# LED.net
KiCad netlist of a schematic drawn in Altium Designer
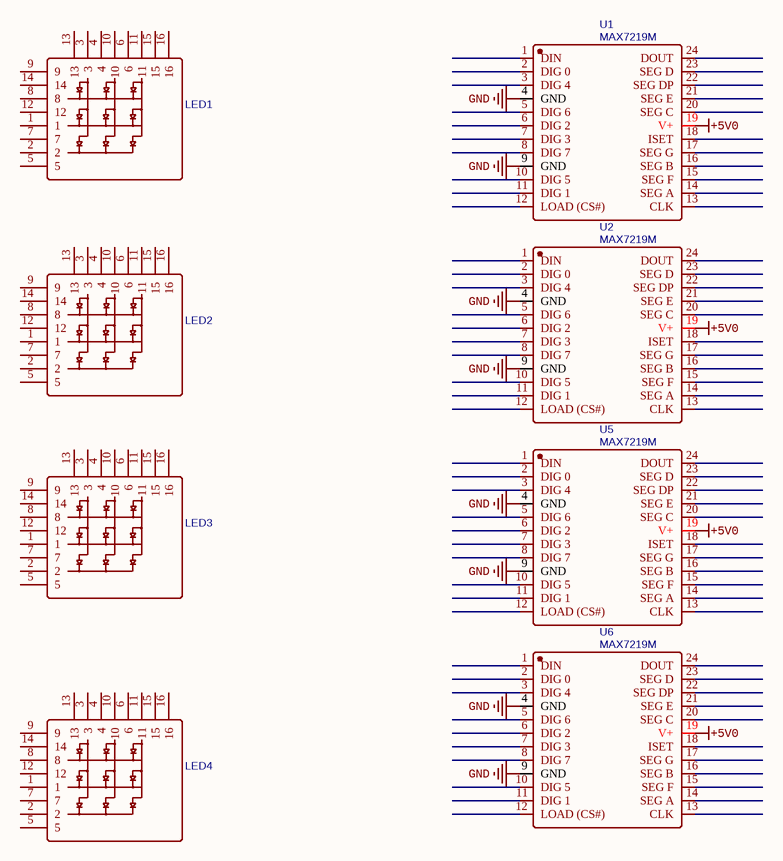
[diagram p0: LED.SchDoc]

(export (version "E")
  (design (tool "Eeschema 10.0.6"))
  (components
    (comp (ref "LED1")
      (value "~")
      (footprint "matrix_led")
      (fields
        (field (name "BOM_SUPPLIER PART") "C225986")
        (field (name "BOM_MANUFACTURER PART") "SLD0888DWC1BY")
        (field (name "CONTRIBUTOR") "LCSC")
      )
      (libsource (lib "altium-import") (part "root_0_SLD0888DWC1BY_"))
    )
    (comp (ref "LED2")
      (value "~")
      (footprint "matrix_led")
      (fields
        (field (name "BOM_SUPPLIER PART") "C225986")
        (field (name "BOM_MANUFACTURER PART") "SLD0888DWC1BY")
        (field (name "CONTRIBUTOR") "LCSC")
      )
      (libsource (lib "altium-import") (part "root_0_SLD0888DWC1BY_"))
    )
    (comp (ref "LED3")
      (value "~")
      (footprint "matrix_led")
      (fields
        (field (name "BOM_SUPPLIER PART") "C225986")
        (field (name "BOM_MANUFACTURER PART") "SLD0888DWC1BY")
        (field (name "CONTRIBUTOR") "LCSC")
      )
      (libsource (lib "altium-import") (part "root_0_SLD0888DWC1BY_"))
    )
    (comp (ref "LED4")
      (value "~")
      (footprint "matrix_led")
      (fields
        (field (name "BOM_SUPPLIER PART") "C225986")
        (field (name "BOM_MANUFACTURER PART") "SLD0888DWC1BY")
        (field (name "CONTRIBUTOR") "LCSC")
      )
      (libsource (lib "altium-import") (part "root_0_SLD0888DWC1BY_"))
    )
    (comp (ref "U1")
      (value "MAX7219M")
      (footprint "SOP-24_300mil")
      (fields (field (name "BOM_SUPPLIER PART") "C492110") (field (name "CONTRIBUTOR") "LCSC"))
      (libsource (lib "altium-import") (part "root_0_MAX7219M_"))
    )
    (comp (ref "U2")
      (value "MAX7219M")
      (footprint "SOP-24_300mil")
      (fields (field (name "BOM_SUPPLIER PART") "C492110") (field (name "CONTRIBUTOR") "LCSC"))
      (libsource (lib "altium-import") (part "root_0_MAX7219M_"))
    )
    (comp (ref "U5")
      (value "MAX7219M")
      (footprint "SOP-24_300mil")
      (fields (field (name "BOM_SUPPLIER PART") "C492110") (field (name "CONTRIBUTOR") "LCSC"))
      (libsource (lib "altium-import") (part "root_0_MAX7219M_"))
    )
    (comp (ref "U6")
      (value "MAX7219M")
      (footprint "SOP-24_300mil")
      (fields (field (name "BOM_SUPPLIER PART") "C492110") (field (name "CONTRIBUTOR") "LCSC"))
      (libsource (lib "altium-import") (part "root_0_MAX7219M_"))
    )
  )
  (nets
    (net (code "1") (name "+5V0") (class "Default")
      (node (ref "U1") (pin "19") (pinfunction "V+_19") (pintype "passive"))
      (node (ref "U2") (pin "19") (pinfunction "V+_19") (pintype "passive"))
      (node (ref "U5") (pin "19") (pinfunction "V+_19") (pintype "passive"))
      (node (ref "U6") (pin "19") (pinfunction "V+_19") (pintype "passive"))
    )
    (net (code "2") (name "GND") (class "Default")
      (node (ref "U1") (pin "4") (pinfunction "GND_4") (pintype "passive"))
      (node (ref "U1") (pin "9") (pinfunction "GND_9") (pintype "passive"))
      (node (ref "U2") (pin "4") (pinfunction "GND_4") (pintype "passive"))
      (node (ref "U2") (pin "9") (pinfunction "GND_9") (pintype "passive"))
      (node (ref "U5") (pin "4") (pinfunction "GND_4") (pintype "passive"))
      (node (ref "U5") (pin "9") (pinfunction "GND_9") (pintype "passive"))
      (node (ref "U6") (pin "4") (pinfunction "GND_4") (pintype "passive"))
      (node (ref "U6") (pin "9") (pinfunction "GND_9") (pintype "passive"))
    )
    (net (code "3") (name "unconnected-(LED1-Pad1)") (class "Default")
      (node (ref "LED1") (pin "1") (pinfunction "1_1") (pintype "passive"))
    )
    (net (code "4") (name "unconnected-(LED1-Pad2)") (class "Default")
      (node (ref "LED1") (pin "2") (pinfunction "2_2") (pintype "passive"))
    )
    (net (code "5") (name "unconnected-(LED1-Pad3)") (class "Default")
      (node (ref "LED1") (pin "3") (pinfunction "3_3") (pintype "passive"))
    )
    (net (code "6") (name "unconnected-(LED1-Pad4)") (class "Default")
      (node (ref "LED1") (pin "4") (pinfunction "4_4") (pintype "passive"))
    )
    (net (code "7") (name "unconnected-(LED1-Pad5)") (class "Default")
      (node (ref "LED1") (pin "5") (pinfunction "5_5") (pintype "passive"))
    )
    (net (code "8") (name "unconnected-(LED1-Pad6)") (class "Default")
      (node (ref "LED1") (pin "6") (pinfunction "6_6") (pintype "passive"))
    )
    (net (code "9") (name "unconnected-(LED1-Pad7)") (class "Default")
      (node (ref "LED1") (pin "7") (pinfunction "7_7") (pintype "passive"))
    )
    (net (code "10") (name "unconnected-(LED1-Pad8)") (class "Default")
      (node (ref "LED1") (pin "8") (pinfunction "8_8") (pintype "passive"))
    )
    (net (code "11") (name "unconnected-(LED1-Pad9)") (class "Default")
      (node (ref "LED1") (pin "9") (pinfunction "9_9") (pintype "passive"))
    )
    (net (code "12") (name "unconnected-(LED1-Pad10)") (class "Default")
      (node (ref "LED1") (pin "10") (pinfunction "10_10") (pintype "passive"))
    )
    (net (code "13") (name "unconnected-(LED1-Pad11)") (class "Default")
      (node (ref "LED1") (pin "11") (pinfunction "11_11") (pintype "passive"))
    )
    (net (code "14") (name "unconnected-(LED1-Pad12)") (class "Default")
      (node (ref "LED1") (pin "12") (pinfunction "12_12") (pintype "passive"))
    )
    (net (code "15") (name "unconnected-(LED1-Pad13)") (class "Default")
      (node (ref "LED1") (pin "13") (pinfunction "13_13") (pintype "passive"))
    )
    (net (code "16") (name "unconnected-(LED1-Pad14)") (class "Default")
      (node (ref "LED1") (pin "14") (pinfunction "14_14") (pintype "passive"))
    )
    (net (code "17") (name "unconnected-(LED1-Pad15)") (class "Default")
      (node (ref "LED1") (pin "15") (pinfunction "15_15") (pintype "passive"))
    )
    (net (code "18") (name "unconnected-(LED1-Pad16)") (class "Default")
      (node (ref "LED1") (pin "16") (pinfunction "16_16") (pintype "passive"))
    )
    (net (code "19") (name "unconnected-(LED2-Pad1)") (class "Default")
      (node (ref "LED2") (pin "1") (pinfunction "1_1") (pintype "passive"))
    )
    (net (code "20") (name "unconnected-(LED2-Pad2)") (class "Default")
      (node (ref "LED2") (pin "2") (pinfunction "2_2") (pintype "passive"))
    )
    (net (code "21") (name "unconnected-(LED2-Pad3)") (class "Default")
      (node (ref "LED2") (pin "3") (pinfunction "3_3") (pintype "passive"))
    )
    (net (code "22") (name "unconnected-(LED2-Pad4)") (class "Default")
      (node (ref "LED2") (pin "4") (pinfunction "4_4") (pintype "passive"))
    )
    (net (code "23") (name "unconnected-(LED2-Pad5)") (class "Default")
      (node (ref "LED2") (pin "5") (pinfunction "5_5") (pintype "passive"))
    )
    (net (code "24") (name "unconnected-(LED2-Pad6)") (class "Default")
      (node (ref "LED2") (pin "6") (pinfunction "6_6") (pintype "passive"))
    )
    (net (code "25") (name "unconnected-(LED2-Pad7)") (class "Default")
      (node (ref "LED2") (pin "7") (pinfunction "7_7") (pintype "passive"))
    )
    (net (code "26") (name "unconnected-(LED2-Pad8)") (class "Default")
      (node (ref "LED2") (pin "8") (pinfunction "8_8") (pintype "passive"))
    )
    (net (code "27") (name "unconnected-(LED2-Pad9)") (class "Default")
      (node (ref "LED2") (pin "9") (pinfunction "9_9") (pintype "passive"))
    )
    (net (code "28") (name "unconnected-(LED2-Pad10)") (class "Default")
      (node (ref "LED2") (pin "10") (pinfunction "10_10") (pintype "passive"))
    )
    (net (code "29") (name "unconnected-(LED2-Pad11)") (class "Default")
      (node (ref "LED2") (pin "11") (pinfunction "11_11") (pintype "passive"))
    )
    (net (code "30") (name "unconnected-(LED2-Pad12)") (class "Default")
      (node (ref "LED2") (pin "12") (pinfunction "12_12") (pintype "passive"))
    )
    (net (code "31") (name "unconnected-(LED2-Pad13)") (class "Default")
      (node (ref "LED2") (pin "13") (pinfunction "13_13") (pintype "passive"))
    )
    (net (code "32") (name "unconnected-(LED2-Pad14)") (class "Default")
      (node (ref "LED2") (pin "14") (pinfunction "14_14") (pintype "passive"))
    )
    (net (code "33") (name "unconnected-(LED2-Pad15)") (class "Default")
      (node (ref "LED2") (pin "15") (pinfunction "15_15") (pintype "passive"))
    )
    (net (code "34") (name "unconnected-(LED2-Pad16)") (class "Default")
      (node (ref "LED2") (pin "16") (pinfunction "16_16") (pintype "passive"))
    )
    (net (code "35") (name "unconnected-(LED3-Pad1)") (class "Default")
      (node (ref "LED3") (pin "1") (pinfunction "1_1") (pintype "passive"))
    )
    (net (code "36") (name "unconnected-(LED3-Pad2)") (class "Default")
      (node (ref "LED3") (pin "2") (pinfunction "2_2") (pintype "passive"))
    )
    (net (code "37") (name "unconnected-(LED3-Pad3)") (class "Default")
      (node (ref "LED3") (pin "3") (pinfunction "3_3") (pintype "passive"))
    )
    (net (code "38") (name "unconnected-(LED3-Pad4)") (class "Default")
      (node (ref "LED3") (pin "4") (pinfunction "4_4") (pintype "passive"))
    )
    (net (code "39") (name "unconnected-(LED3-Pad5)") (class "Default")
      (node (ref "LED3") (pin "5") (pinfunction "5_5") (pintype "passive"))
    )
    (net (code "40") (name "unconnected-(LED3-Pad6)") (class "Default")
      (node (ref "LED3") (pin "6") (pinfunction "6_6") (pintype "passive"))
    )
    (net (code "41") (name "unconnected-(LED3-Pad7)") (class "Default")
      (node (ref "LED3") (pin "7") (pinfunction "7_7") (pintype "passive"))
    )
    (net (code "42") (name "unconnected-(LED3-Pad8)") (class "Default")
      (node (ref "LED3") (pin "8") (pinfunction "8_8") (pintype "passive"))
    )
    (net (code "43") (name "unconnected-(LED3-Pad9)") (class "Default")
      (node (ref "LED3") (pin "9") (pinfunction "9_9") (pintype "passive"))
    )
    (net (code "44") (name "unconnected-(LED3-Pad10)") (class "Default")
      (node (ref "LED3") (pin "10") (pinfunction "10_10") (pintype "passive"))
    )
    (net (code "45") (name "unconnected-(LED3-Pad11)") (class "Default")
      (node (ref "LED3") (pin "11") (pinfunction "11_11") (pintype "passive"))
    )
    (net (code "46") (name "unconnected-(LED3-Pad12)") (class "Default")
      (node (ref "LED3") (pin "12") (pinfunction "12_12") (pintype "passive"))
    )
    (net (code "47") (name "unconnected-(LED3-Pad13)") (class "Default")
      (node (ref "LED3") (pin "13") (pinfunction "13_13") (pintype "passive"))
    )
    (net (code "48") (name "unconnected-(LED3-Pad14)") (class "Default")
      (node (ref "LED3") (pin "14") (pinfunction "14_14") (pintype "passive"))
    )
    (net (code "49") (name "unconnected-(LED3-Pad15)") (class "Default")
      (node (ref "LED3") (pin "15") (pinfunction "15_15") (pintype "passive"))
    )
    (net (code "50") (name "unconnected-(LED3-Pad16)") (class "Default")
      (node (ref "LED3") (pin "16") (pinfunction "16_16") (pintype "passive"))
    )
    (net (code "51") (name "unconnected-(LED4-Pad1)") (class "Default")
      (node (ref "LED4") (pin "1") (pinfunction "1_1") (pintype "passive"))
    )
    (net (code "52") (name "unconnected-(LED4-Pad2)") (class "Default")
      (node (ref "LED4") (pin "2") (pinfunction "2_2") (pintype "passive"))
    )
    (net (code "53") (name "unconnected-(LED4-Pad3)") (class "Default")
      (node (ref "LED4") (pin "3") (pinfunction "3_3") (pintype "passive"))
    )
    (net (code "54") (name "unconnected-(LED4-Pad4)") (class "Default")
      (node (ref "LED4") (pin "4") (pinfunction "4_4") (pintype "passive"))
    )
    (net (code "55") (name "unconnected-(LED4-Pad5)") (class "Default")
      (node (ref "LED4") (pin "5") (pinfunction "5_5") (pintype "passive"))
    )
    (net (code "56") (name "unconnected-(LED4-Pad6)") (class "Default")
      (node (ref "LED4") (pin "6") (pinfunction "6_6") (pintype "passive"))
    )
    (net (code "57") (name "unconnected-(LED4-Pad7)") (class "Default")
      (node (ref "LED4") (pin "7") (pinfunction "7_7") (pintype "passive"))
    )
    (net (code "58") (name "unconnected-(LED4-Pad8)") (class "Default")
      (node (ref "LED4") (pin "8") (pinfunction "8_8") (pintype "passive"))
    )
    (net (code "59") (name "unconnected-(LED4-Pad9)") (class "Default")
      (node (ref "LED4") (pin "9") (pinfunction "9_9") (pintype "passive"))
    )
    (net (code "60") (name "unconnected-(LED4-Pad10)") (class "Default")
      (node (ref "LED4") (pin "10") (pinfunction "10_10") (pintype "passive"))
    )
    (net (code "61") (name "unconnected-(LED4-Pad11)") (class "Default")
      (node (ref "LED4") (pin "11") (pinfunction "11_11") (pintype "passive"))
    )
    (net (code "62") (name "unconnected-(LED4-Pad12)") (class "Default")
      (node (ref "LED4") (pin "12") (pinfunction "12_12") (pintype "passive"))
    )
    (net (code "63") (name "unconnected-(LED4-Pad13)") (class "Default")
      (node (ref "LED4") (pin "13") (pinfunction "13_13") (pintype "passive"))
    )
    (net (code "64") (name "unconnected-(LED4-Pad14)") (class "Default")
      (node (ref "LED4") (pin "14") (pinfunction "14_14") (pintype "passive"))
    )
    (net (code "65") (name "unconnected-(LED4-Pad15)") (class "Default")
      (node (ref "LED4") (pin "15") (pinfunction "15_15") (pintype "passive"))
    )
    (net (code "66") (name "unconnected-(LED4-Pad16)") (class "Default")
      (node (ref "LED4") (pin "16") (pinfunction "16_16") (pintype "passive"))
    )
    (net (code "67") (name "unconnected-(U1-CLK-Pad13)") (class "Default")
      (node (ref "U1") (pin "13") (pinfunction "CLK_13") (pintype "passive"))
    )
    (net (code "68") (name "unconnected-(U1-DIG_0-Pad2)") (class "Default")
      (node (ref "U1") (pin "2") (pinfunction "DIG_0_2") (pintype "passive"))
    )
    (net (code "69") (name "unconnected-(U1-DIG_1-Pad11)") (class "Default")
      (node (ref "U1") (pin "11") (pinfunction "DIG_1_11") (pintype "passive"))
    )
    (net (code "70") (name "unconnected-(U1-DIG_2-Pad6)") (class "Default")
      (node (ref "U1") (pin "6") (pinfunction "DIG_2_6") (pintype "passive"))
    )
    (net (code "71") (name "unconnected-(U1-DIG_3-Pad7)") (class "Default")
      (node (ref "U1") (pin "7") (pinfunction "DIG_3_7") (pintype "passive"))
    )
    (net (code "72") (name "unconnected-(U1-DIG_4-Pad3)") (class "Default")
      (node (ref "U1") (pin "3") (pinfunction "DIG_4_3") (pintype "passive"))
    )
    (net (code "73") (name "unconnected-(U1-DIG_5-Pad10)") (class "Default")
      (node (ref "U1") (pin "10") (pinfunction "DIG_5_10") (pintype "passive"))
    )
    (net (code "74") (name "unconnected-(U1-DIG_6-Pad5)") (class "Default")
      (node (ref "U1") (pin "5") (pinfunction "DIG_6_5") (pintype "passive"))
    )
    (net (code "75") (name "unconnected-(U1-DIG_7-Pad8)") (class "Default")
      (node (ref "U1") (pin "8") (pinfunction "DIG_7_8") (pintype "passive"))
    )
    (net (code "76") (name "unconnected-(U1-DIN-Pad1)") (class "Default")
      (node (ref "U1") (pin "1") (pinfunction "DIN_1") (pintype "passive"))
    )
    (net (code "77") (name "unconnected-(U1-DOUT-Pad24)") (class "Default")
      (node (ref "U1") (pin "24") (pinfunction "DOUT_24") (pintype "passive"))
    )
    (net (code "78") (name "unconnected-(U1-ISET-Pad18)") (class "Default")
      (node (ref "U1") (pin "18") (pinfunction "ISET_18") (pintype "passive"))
    )
    (net (code "79") (name "unconnected-(U1-LOAD_(CS#)-Pad12)") (class "Default")
      (node (ref "U1") (pin "12") (pinfunction "LOAD_(CS#)_12") (pintype "passive"))
    )
    (net (code "80") (name "unconnected-(U1-SEG_A-Pad14)") (class "Default")
      (node (ref "U1") (pin "14") (pinfunction "SEG_A_14") (pintype "passive"))
    )
    (net (code "81") (name "unconnected-(U1-SEG_B-Pad16)") (class "Default")
      (node (ref "U1") (pin "16") (pinfunction "SEG_B_16") (pintype "passive"))
    )
    (net (code "82") (name "unconnected-(U1-SEG_C-Pad20)") (class "Default")
      (node (ref "U1") (pin "20") (pinfunction "SEG_C_20") (pintype "passive"))
    )
    (net (code "83") (name "unconnected-(U1-SEG_D-Pad23)") (class "Default")
      (node (ref "U1") (pin "23") (pinfunction "SEG_D_23") (pintype "passive"))
    )
    (net (code "84") (name "unconnected-(U1-SEG_DP-Pad22)") (class "Default")
      (node (ref "U1") (pin "22") (pinfunction "SEG_DP_22") (pintype "passive"))
    )
    (net (code "85") (name "unconnected-(U1-SEG_E-Pad21)") (class "Default")
      (node (ref "U1") (pin "21") (pinfunction "SEG_E_21") (pintype "passive"))
    )
    (net (code "86") (name "unconnected-(U1-SEG_F-Pad15)") (class "Default")
      (node (ref "U1") (pin "15") (pinfunction "SEG_F_15") (pintype "passive"))
    )
    (net (code "87") (name "unconnected-(U1-SEG_G-Pad17)") (class "Default")
      (node (ref "U1") (pin "17") (pinfunction "SEG_G_17") (pintype "passive"))
    )
    (net (code "88") (name "unconnected-(U2-CLK-Pad13)") (class "Default")
      (node (ref "U2") (pin "13") (pinfunction "CLK_13") (pintype "passive"))
    )
    (net (code "89") (name "unconnected-(U2-DIG_0-Pad2)") (class "Default")
      (node (ref "U2") (pin "2") (pinfunction "DIG_0_2") (pintype "passive"))
    )
    (net (code "90") (name "unconnected-(U2-DIG_1-Pad11)") (class "Default")
      (node (ref "U2") (pin "11") (pinfunction "DIG_1_11") (pintype "passive"))
    )
    (net (code "91") (name "unconnected-(U2-DIG_2-Pad6)") (class "Default")
      (node (ref "U2") (pin "6") (pinfunction "DIG_2_6") (pintype "passive"))
    )
    (net (code "92") (name "unconnected-(U2-DIG_3-Pad7)") (class "Default")
      (node (ref "U2") (pin "7") (pinfunction "DIG_3_7") (pintype "passive"))
    )
    (net (code "93") (name "unconnected-(U2-DIG_4-Pad3)") (class "Default")
      (node (ref "U2") (pin "3") (pinfunction "DIG_4_3") (pintype "passive"))
    )
    (net (code "94") (name "unconnected-(U2-DIG_5-Pad10)") (class "Default")
      (node (ref "U2") (pin "10") (pinfunction "DIG_5_10") (pintype "passive"))
    )
    (net (code "95") (name "unconnected-(U2-DIG_6-Pad5)") (class "Default")
      (node (ref "U2") (pin "5") (pinfunction "DIG_6_5") (pintype "passive"))
    )
    (net (code "96") (name "unconnected-(U2-DIG_7-Pad8)") (class "Default")
      (node (ref "U2") (pin "8") (pinfunction "DIG_7_8") (pintype "passive"))
    )
    (net (code "97") (name "unconnected-(U2-DIN-Pad1)") (class "Default")
      (node (ref "U2") (pin "1") (pinfunction "DIN_1") (pintype "passive"))
    )
    (net (code "98") (name "unconnected-(U2-DOUT-Pad24)") (class "Default")
      (node (ref "U2") (pin "24") (pinfunction "DOUT_24") (pintype "passive"))
    )
    (net (code "99") (name "unconnected-(U2-ISET-Pad18)") (class "Default")
      (node (ref "U2") (pin "18") (pinfunction "ISET_18") (pintype "passive"))
    )
    (net (code "100") (name "unconnected-(U2-LOAD_(CS#)-Pad12)") (class "Default")
      (node (ref "U2") (pin "12") (pinfunction "LOAD_(CS#)_12") (pintype "passive"))
    )
    (net (code "101") (name "unconnected-(U2-SEG_A-Pad14)") (class "Default")
      (node (ref "U2") (pin "14") (pinfunction "SEG_A_14") (pintype "passive"))
    )
    (net (code "102") (name "unconnected-(U2-SEG_B-Pad16)") (class "Default")
      (node (ref "U2") (pin "16") (pinfunction "SEG_B_16") (pintype "passive"))
    )
    (net (code "103") (name "unconnected-(U2-SEG_C-Pad20)") (class "Default")
      (node (ref "U2") (pin "20") (pinfunction "SEG_C_20") (pintype "passive"))
    )
    (net (code "104") (name "unconnected-(U2-SEG_D-Pad23)") (class "Default")
      (node (ref "U2") (pin "23") (pinfunction "SEG_D_23") (pintype "passive"))
    )
    (net (code "105") (name "unconnected-(U2-SEG_DP-Pad22)") (class "Default")
      (node (ref "U2") (pin "22") (pinfunction "SEG_DP_22") (pintype "passive"))
    )
    (net (code "106") (name "unconnected-(U2-SEG_E-Pad21)") (class "Default")
      (node (ref "U2") (pin "21") (pinfunction "SEG_E_21") (pintype "passive"))
    )
    (net (code "107") (name "unconnected-(U2-SEG_F-Pad15)") (class "Default")
      (node (ref "U2") (pin "15") (pinfunction "SEG_F_15") (pintype "passive"))
    )
    (net (code "108") (name "unconnected-(U2-SEG_G-Pad17)") (class "Default")
      (node (ref "U2") (pin "17") (pinfunction "SEG_G_17") (pintype "passive"))
    )
    (net (code "109") (name "unconnected-(U5-CLK-Pad13)") (class "Default")
      (node (ref "U5") (pin "13") (pinfunction "CLK_13") (pintype "passive"))
    )
    (net (code "110") (name "unconnected-(U5-DIG_0-Pad2)") (class "Default")
      (node (ref "U5") (pin "2") (pinfunction "DIG_0_2") (pintype "passive"))
    )
    (net (code "111") (name "unconnected-(U5-DIG_1-Pad11)") (class "Default")
      (node (ref "U5") (pin "11") (pinfunction "DIG_1_11") (pintype "passive"))
    )
    (net (code "112") (name "unconnected-(U5-DIG_2-Pad6)") (class "Default")
      (node (ref "U5") (pin "6") (pinfunction "DIG_2_6") (pintype "passive"))
    )
    (net (code "113") (name "unconnected-(U5-DIG_3-Pad7)") (class "Default")
      (node (ref "U5") (pin "7") (pinfunction "DIG_3_7") (pintype "passive"))
    )
    (net (code "114") (name "unconnected-(U5-DIG_4-Pad3)") (class "Default")
      (node (ref "U5") (pin "3") (pinfunction "DIG_4_3") (pintype "passive"))
    )
    (net (code "115") (name "unconnected-(U5-DIG_5-Pad10)") (class "Default")
      (node (ref "U5") (pin "10") (pinfunction "DIG_5_10") (pintype "passive"))
    )
    (net (code "116") (name "unconnected-(U5-DIG_6-Pad5)") (class "Default")
      (node (ref "U5") (pin "5") (pinfunction "DIG_6_5") (pintype "passive"))
    )
    (net (code "117") (name "unconnected-(U5-DIG_7-Pad8)") (class "Default")
      (node (ref "U5") (pin "8") (pinfunction "DIG_7_8") (pintype "passive"))
    )
    (net (code "118") (name "unconnected-(U5-DIN-Pad1)") (class "Default")
      (node (ref "U5") (pin "1") (pinfunction "DIN_1") (pintype "passive"))
    )
    (net (code "119") (name "unconnected-(U5-DOUT-Pad24)") (class "Default")
      (node (ref "U5") (pin "24") (pinfunction "DOUT_24") (pintype "passive"))
    )
    (net (code "120") (name "unconnected-(U5-ISET-Pad18)") (class "Default")
      (node (ref "U5") (pin "18") (pinfunction "ISET_18") (pintype "passive"))
    )
    (net (code "121") (name "unconnected-(U5-LOAD_(CS#)-Pad12)") (class "Default")
      (node (ref "U5") (pin "12") (pinfunction "LOAD_(CS#)_12") (pintype "passive"))
    )
    (net (code "122") (name "unconnected-(U5-SEG_A-Pad14)") (class "Default")
      (node (ref "U5") (pin "14") (pinfunction "SEG_A_14") (pintype "passive"))
    )
    (net (code "123") (name "unconnected-(U5-SEG_B-Pad16)") (class "Default")
      (node (ref "U5") (pin "16") (pinfunction "SEG_B_16") (pintype "passive"))
    )
    (net (code "124") (name "unconnected-(U5-SEG_C-Pad20)") (class "Default")
      (node (ref "U5") (pin "20") (pinfunction "SEG_C_20") (pintype "passive"))
    )
    (net (code "125") (name "unconnected-(U5-SEG_D-Pad23)") (class "Default")
      (node (ref "U5") (pin "23") (pinfunction "SEG_D_23") (pintype "passive"))
    )
    (net (code "126") (name "unconnected-(U5-SEG_DP-Pad22)") (class "Default")
      (node (ref "U5") (pin "22") (pinfunction "SEG_DP_22") (pintype "passive"))
    )
    (net (code "127") (name "unconnected-(U5-SEG_E-Pad21)") (class "Default")
      (node (ref "U5") (pin "21") (pinfunction "SEG_E_21") (pintype "passive"))
    )
    (net (code "128") (name "unconnected-(U5-SEG_F-Pad15)") (class "Default")
      (node (ref "U5") (pin "15") (pinfunction "SEG_F_15") (pintype "passive"))
    )
    (net (code "129") (name "unconnected-(U5-SEG_G-Pad17)") (class "Default")
      (node (ref "U5") (pin "17") (pinfunction "SEG_G_17") (pintype "passive"))
    )
    (net (code "130") (name "unconnected-(U6-CLK-Pad13)") (class "Default")
      (node (ref "U6") (pin "13") (pinfunction "CLK_13") (pintype "passive"))
    )
    (net (code "131") (name "unconnected-(U6-DIG_0-Pad2)") (class "Default")
      (node (ref "U6") (pin "2") (pinfunction "DIG_0_2") (pintype "passive"))
    )
    (net (code "132") (name "unconnected-(U6-DIG_1-Pad11)") (class "Default")
      (node (ref "U6") (pin "11") (pinfunction "DIG_1_11") (pintype "passive"))
    )
    (net (code "133") (name "unconnected-(U6-DIG_2-Pad6)") (class "Default")
      (node (ref "U6") (pin "6") (pinfunction "DIG_2_6") (pintype "passive"))
    )
    (net (code "134") (name "unconnected-(U6-DIG_3-Pad7)") (class "Default")
      (node (ref "U6") (pin "7") (pinfunction "DIG_3_7") (pintype "passive"))
    )
    (net (code "135") (name "unconnected-(U6-DIG_4-Pad3)") (class "Default")
      (node (ref "U6") (pin "3") (pinfunction "DIG_4_3") (pintype "passive"))
    )
    (net (code "136") (name "unconnected-(U6-DIG_5-Pad10)") (class "Default")
      (node (ref "U6") (pin "10") (pinfunction "DIG_5_10") (pintype "passive"))
    )
    (net (code "137") (name "unconnected-(U6-DIG_6-Pad5)") (class "Default")
      (node (ref "U6") (pin "5") (pinfunction "DIG_6_5") (pintype "passive"))
    )
    (net (code "138") (name "unconnected-(U6-DIG_7-Pad8)") (class "Default")
      (node (ref "U6") (pin "8") (pinfunction "DIG_7_8") (pintype "passive"))
    )
    (net (code "139") (name "unconnected-(U6-DIN-Pad1)") (class "Default")
      (node (ref "U6") (pin "1") (pinfunction "DIN_1") (pintype "passive"))
    )
    (net (code "140") (name "unconnected-(U6-DOUT-Pad24)") (class "Default")
      (node (ref "U6") (pin "24") (pinfunction "DOUT_24") (pintype "passive"))
    )
    (net (code "141") (name "unconnected-(U6-ISET-Pad18)") (class "Default")
      (node (ref "U6") (pin "18") (pinfunction "ISET_18") (pintype "passive"))
    )
    (net (code "142") (name "unconnected-(U6-LOAD_(CS#)-Pad12)") (class "Default")
      (node (ref "U6") (pin "12") (pinfunction "LOAD_(CS#)_12") (pintype "passive"))
    )
    (net (code "143") (name "unconnected-(U6-SEG_A-Pad14)") (class "Default")
      (node (ref "U6") (pin "14") (pinfunction "SEG_A_14") (pintype "passive"))
    )
    (net (code "144") (name "unconnected-(U6-SEG_B-Pad16)") (class "Default")
      (node (ref "U6") (pin "16") (pinfunction "SEG_B_16") (pintype "passive"))
    )
    (net (code "145") (name "unconnected-(U6-SEG_C-Pad20)") (class "Default")
      (node (ref "U6") (pin "20") (pinfunction "SEG_C_20") (pintype "passive"))
    )
    (net (code "146") (name "unconnected-(U6-SEG_D-Pad23)") (class "Default")
      (node (ref "U6") (pin "23") (pinfunction "SEG_D_23") (pintype "passive"))
    )
    (net (code "147") (name "unconnected-(U6-SEG_DP-Pad22)") (class "Default")
      (node (ref "U6") (pin "22") (pinfunction "SEG_DP_22") (pintype "passive"))
    )
    (net (code "148") (name "unconnected-(U6-SEG_E-Pad21)") (class "Default")
      (node (ref "U6") (pin "21") (pinfunction "SEG_E_21") (pintype "passive"))
    )
    (net (code "149") (name "unconnected-(U6-SEG_F-Pad15)") (class "Default")
      (node (ref "U6") (pin "15") (pinfunction "SEG_F_15") (pintype "passive"))
    )
    (net (code "150") (name "unconnected-(U6-SEG_G-Pad17)") (class "Default")
      (node (ref "U6") (pin "17") (pinfunction "SEG_G_17") (pintype "passive"))
    )
  )
)
